# 7_-GSM_MODEM_MAIN.net
KiCad netlist of a schematic drawn in Altium Designer
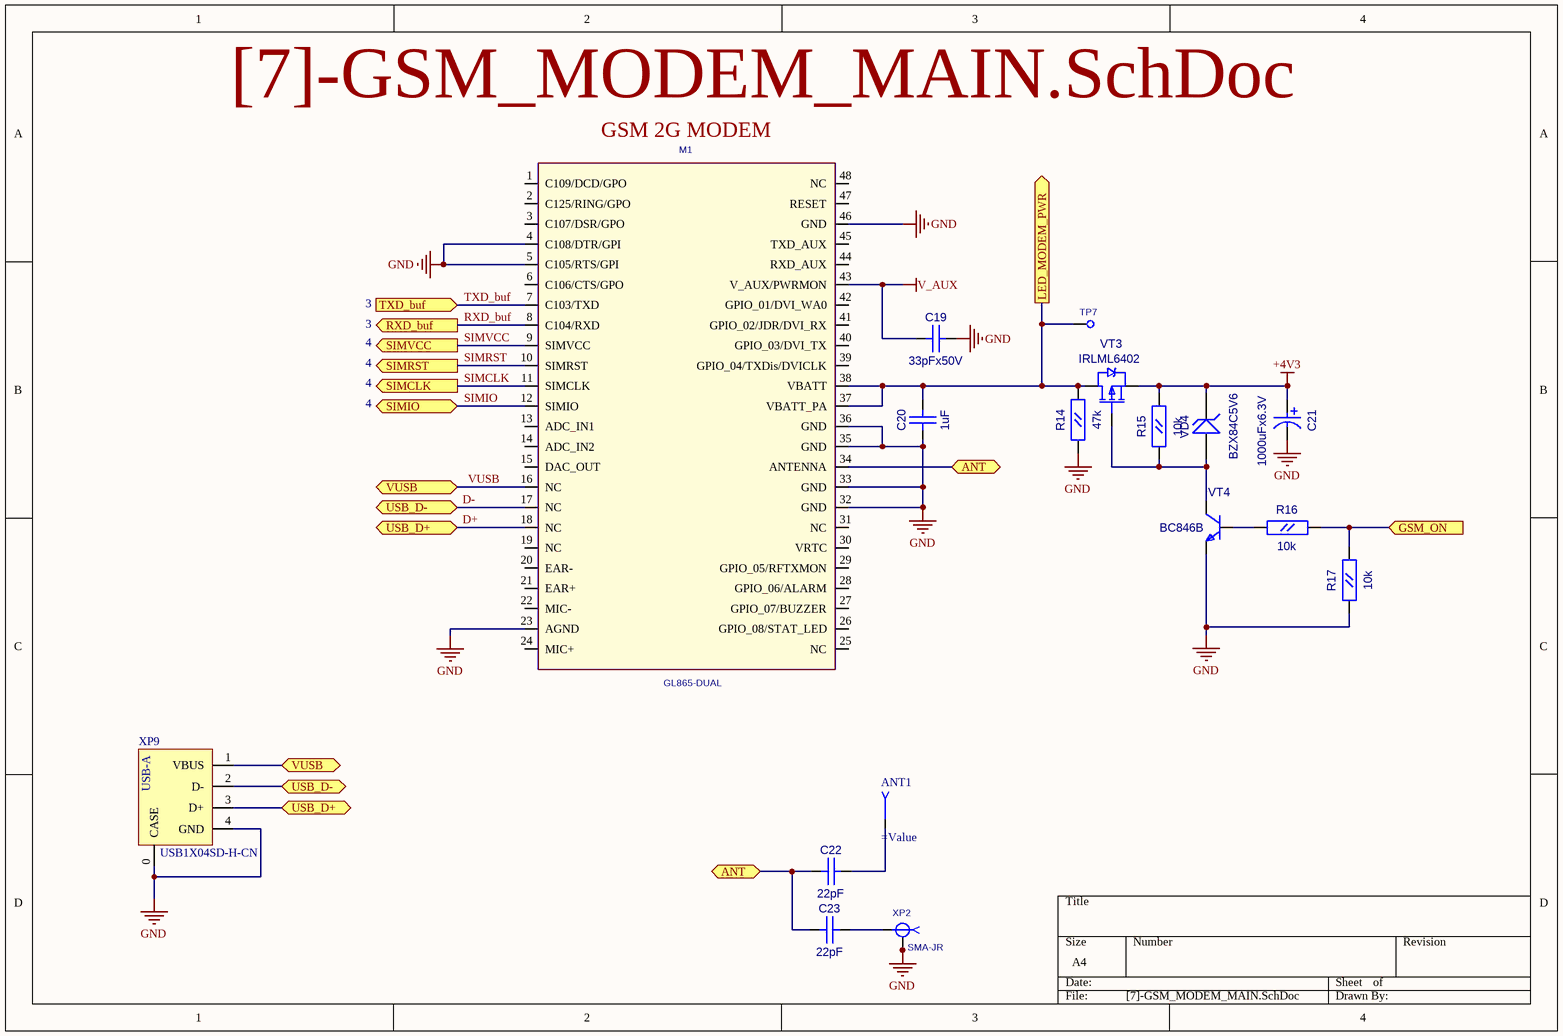
[diagram p0: [7]-GSM_MODEM_MAIN.SchDoc]

(export (version "E")
  (design (tool "Eeschema 10.0.6"))
  (components
    (comp (ref "ANT1")
      (value "~")
      (footprint "GSM_ANTENNA_MEANDER")
      (description "900-1800 Meandered GSM antenna 1.6mm FR4")
      (libsource (lib "fizik_lib") (part "GSM_ANTENNA_MEANDR"))
    )
    (comp (ref "C19")
      (value "33pFx50V")
      (footprint "CC0603")
      (description "CC0603")
      (libsource (lib "gprs_modem_2") (part "CC0603"))
    )
    (comp (ref "C20")
      (value "1uF")
      (footprint "CC0603")
      (description "CC0603")
      (libsource (lib "gprs_modem_2") (part "CC0603"))
    )
    (comp (ref "C21")
      (value "1000uFx6.3V")
      (footprint "CC8X3.5")
      (description "CAP0.35")
      (libsource (lib "fizik_lib") (part "CAP0.35"))
    )
    (comp (ref "C22")
      (value "22pF")
      (footprint "CC0603")
      (description "CC0603")
      (libsource (lib "gprs_modem_2") (part "CC0603"))
    )
    (comp (ref "C23")
      (value "22pF")
      (footprint "CC0603")
      (description "CC0603")
      (libsource (lib "gprs_modem_2") (part "CC0603"))
    )
    (comp (ref "M1")
      (value "GL865-DUAL")
      (footprint "GL868-DUAL")
      (description "GL868-DUAL")
      (libsource (lib "gprs_modem_2") (part "GL868-DUAL"))
    )
    (comp (ref "R14")
      (value "47k")
      (footprint "RC0603")
      (description "RC0603")
      (libsource (lib "gprs_modem_2") (part "RC0603"))
    )
    (comp (ref "R15")
      (value "10k")
      (footprint "RC0603")
      (description "RC0603")
      (libsource (lib "gprs_modem_2") (part "RC0603"))
    )
    (comp (ref "R16")
      (value "10k")
      (footprint "RC0603")
      (description "RC0603")
      (libsource (lib "gprs_modem_2") (part "RC0603"))
    )
    (comp (ref "R17")
      (value "10k")
      (footprint "RC0603")
      (description "RC0603")
      (libsource (lib "gprs_modem_2") (part "RC0603"))
    )
    (comp (ref "TP7")
      (value "TESTPOINT1")
      (footprint "TESTPOINT1")
      (libsource (lib "fizik_lib") (part "TESTPOINT1"))
    )
    (comp (ref "VD4")
      (value "BZX84C5V6")
      (footprint "SOT-23(123)")
      (description "Zener Voltage Regulator Diode")
      (libsource (lib "gprs_modem_2") (part "BZX84"))
    )
    (comp (ref "VT3")
      (value "IRLML6402")
      (footprint "SOT-23(123)")
      (description "HEXFET Power MOSFET")
      (libsource (lib "gprs_modem_2") (part "IRLML6402"))
    )
    (comp (ref "VT4")
      (value "BC846B")
      (footprint "SOT-23(123)")
      (description "BC846BLT1")
      (libsource (lib "gprs_modem_2") (part "BC846BLT1"))
    )
    (comp (ref "XP2") (value "SMA-JR") (footprint "SMA-JR") (libsource (lib "fizik_lib") (part "SMA-JR")))
    (comp (ref "XP9")
      (value "USB1X04SD-H-CN")
      (footprint "USB_A_FRONT")
      (description "Vertical USB connetctor,type A.THR")
      (libsource (lib "fizik_lib") (part "USB_A_VERTICAL"))
    )
  )
  (nets
    (net (code "1") (name "+4V3") (class "Default")
      (node (ref "C21") (pin "1") (pintype "passive"))
      (node (ref "R15") (pin "2") (pinfunction "B_2") (pintype "passive"))
      (node (ref "VD4") (pin "3") (pinfunction "K_3") (pintype "passive"))
      (node (ref "VT3") (pin "2") (pinfunction "S_2") (pintype "passive"))
    )
    (net (code "2") (name "/ANT") (class "Default")
      (node (ref "C22") (pin "1") (pinfunction "A_1") (pintype "passive"))
      (node (ref "C23") (pin "1") (pinfunction "A_1") (pintype "passive"))
      (node (ref "M1") (pin "34") (pinfunction "ANTENNA_34") (pintype "passive"))
    )
    (net (code "3") (name "/D+") (class "Default")
      (node (ref "M1") (pin "18") (pinfunction "NC_18") (pintype "passive"))
      (node (ref "XP9") (pin "3") (pinfunction "D+_3") (pintype "passive"))
    )
    (net (code "4") (name "/D-") (class "Default")
      (node (ref "M1") (pin "17") (pinfunction "NC_17") (pintype "passive"))
      (node (ref "XP9") (pin "2") (pinfunction "D-_2") (pintype "passive"))
    )
    (net (code "5") (name "/GSM_ON") (class "Default")
      (node (ref "R16") (pin "2") (pinfunction "B_2") (pintype "passive"))
      (node (ref "R17") (pin "2") (pinfunction "B_2") (pintype "passive"))
    )
    (net (code "6") (name "/LED_MODEM_PWR") (class "Default")
      (node (ref "C20") (pin "2") (pinfunction "B_2") (pintype "passive"))
      (node (ref "M1") (pin "37") (pinfunction "VBATT_PA_37") (pintype "passive"))
      (node (ref "M1") (pin "38") (pinfunction "VBATT_38") (pintype "passive"))
      (node (ref "R14") (pin "2") (pinfunction "B_2") (pintype "passive"))
      (node (ref "TP7") (pin "1") (pintype "passive"))
      (node (ref "VT3") (pin "3") (pinfunction "D_3") (pintype "passive"))
    )
    (net (code "7") (name "/RXD_buf") (class "Default")
      (node (ref "M1") (pin "8") (pinfunction "C104/RXD_8") (pintype "passive"))
    )
    (net (code "8") (name "/SIMCLK") (class "Default")
      (node (ref "M1") (pin "11") (pinfunction "SIMCLK_11") (pintype "passive"))
    )
    (net (code "9") (name "/SIMIO") (class "Default")
      (node (ref "M1") (pin "12") (pinfunction "SIMIO_12") (pintype "passive"))
    )
    (net (code "10") (name "/SIMRST") (class "Default")
      (node (ref "M1") (pin "10") (pinfunction "SIMRST_10") (pintype "passive"))
    )
    (net (code "11") (name "/SIMVCC") (class "Default")
      (node (ref "M1") (pin "9") (pinfunction "SIMVCC_9") (pintype "passive"))
    )
    (net (code "12") (name "/TXD_buf") (class "Default")
      (node (ref "M1") (pin "7") (pinfunction "C103/TXD_7") (pintype "passive"))
    )
    (net (code "13") (name "/VUSB") (class "Default")
      (node (ref "M1") (pin "16") (pinfunction "NC_16") (pintype "passive"))
      (node (ref "XP9") (pin "1") (pinfunction "VBUS_1") (pintype "passive"))
    )
    (net (code "14") (name "GND") (class "Default")
      (node (ref "C19") (pin "2") (pinfunction "B_2") (pintype "passive"))
      (node (ref "C20") (pin "1") (pinfunction "A_1") (pintype "passive"))
      (node (ref "C21") (pin "2") (pintype "passive"))
      (node (ref "M1") (pin "23") (pinfunction "AGND_23") (pintype "passive"))
      (node (ref "M1") (pin "32") (pinfunction "GND_32") (pintype "passive"))
      (node (ref "M1") (pin "33") (pinfunction "GND_33") (pintype "passive"))
      (node (ref "M1") (pin "35") (pinfunction "GND_35") (pintype "passive"))
      (node (ref "M1") (pin "36") (pinfunction "GND_36") (pintype "passive"))
      (node (ref "M1") (pin "4") (pinfunction "C108/DTR/GPI_4") (pintype "passive"))
      (node (ref "M1") (pin "46") (pinfunction "GND_46") (pintype "passive"))
      (node (ref "M1") (pin "5") (pinfunction "C105/RTS/GPI_5") (pintype "passive"))
      (node (ref "R14") (pin "1") (pinfunction "A_1") (pintype "passive"))
      (node (ref "R17") (pin "1") (pinfunction "A_1") (pintype "passive"))
      (node (ref "VT4") (pin "2") (pinfunction "E_2") (pintype "passive"))
      (node (ref "XP2") (pin "2") (pintype "passive"))
      (node (ref "XP2") (pin "3") (pintype "passive"))
      (node (ref "XP2") (pin "4") (pintype "passive"))
      (node (ref "XP2") (pin "5") (pintype "passive"))
      (node (ref "XP9") (pin "0") (pinfunction "CASE_0") (pintype "passive"))
      (node (ref "XP9") (pin "4") (pinfunction "GND_4") (pintype "passive"))
    )
    (net (code "15") (name "Net-(C22-B)") (class "Default")
      (node (ref "ANT1") (pin "1") (pintype "passive"))
      (node (ref "C22") (pin "2") (pinfunction "B_2") (pintype "passive"))
    )
    (net (code "16") (name "Net-(C23-B)") (class "Default")
      (node (ref "C23") (pin "2") (pinfunction "B_2") (pintype "passive"))
      (node (ref "XP2") (pin "1") (pintype "passive"))
    )
    (net (code "17") (name "Net-(R15-A)") (class "Default")
      (node (ref "R15") (pin "1") (pinfunction "A_1") (pintype "passive"))
      (node (ref "VD4") (pin "1") (pinfunction "A_1") (pintype "passive"))
      (node (ref "VT3") (pin "1") (pinfunction "G_1") (pintype "passive"))
      (node (ref "VT4") (pin "3") (pinfunction "C_3") (pintype "passive"))
    )
    (net (code "18") (name "Net-(R16-A)") (class "Default")
      (node (ref "R16") (pin "1") (pinfunction "A_1") (pintype "passive"))
      (node (ref "VT4") (pin "1") (pinfunction "B_1") (pintype "passive"))
    )
    (net (code "19") (name "V_AUX") (class "Default")
      (node (ref "C19") (pin "1") (pinfunction "A_1") (pintype "passive"))
      (node (ref "M1") (pin "43") (pinfunction "V_AUX/PWRMON_43") (pintype "passive"))
    )
    (net (code "20") (name "unconnected-(M1-ADC_IN1-Pad13)") (class "Default")
      (node (ref "M1") (pin "13") (pinfunction "ADC_IN1_13") (pintype "passive"))
    )
    (net (code "21") (name "unconnected-(M1-ADC_IN2-Pad14)") (class "Default")
      (node (ref "M1") (pin "14") (pinfunction "ADC_IN2_14") (pintype "passive"))
    )
    (net (code "22") (name "unconnected-(M1-C106{slash}CTS{slash}GPO-Pad6)") (class "Default")
      (node (ref "M1") (pin "6") (pinfunction "C106/CTS/GPO_6") (pintype "passive"))
    )
    (net (code "23") (name "unconnected-(M1-C107{slash}DSR{slash}GPO-Pad3)") (class "Default")
      (node (ref "M1") (pin "3") (pinfunction "C107/DSR/GPO_3") (pintype "passive"))
    )
    (net (code "24") (name "unconnected-(M1-C109{slash}DCD{slash}GPO-Pad1)") (class "Default")
      (node (ref "M1") (pin "1") (pinfunction "C109/DCD/GPO_1") (pintype "passive"))
    )
    (net (code "25") (name "unconnected-(M1-C125{slash}RING{slash}GPO-Pad2)") (class "Default")
      (node (ref "M1") (pin "2") (pinfunction "C125/RING/GPO_2") (pintype "passive"))
    )
    (net (code "26") (name "unconnected-(M1-DAC_OUT-Pad15)") (class "Default")
      (node (ref "M1") (pin "15") (pinfunction "DAC_OUT_15") (pintype "passive"))
    )
    (net (code "27") (name "unconnected-(M1-EAR+-Pad21)") (class "Default")
      (node (ref "M1") (pin "21") (pinfunction "EAR+_21") (pintype "passive"))
    )
    (net (code "28") (name "unconnected-(M1-EAR--Pad20)") (class "Default")
      (node (ref "M1") (pin "20") (pinfunction "EAR-_20") (pintype "passive"))
    )
    (net (code "29") (name "unconnected-(M1-GPIO_01{slash}DVI_WA0-Pad42)") (class "Default")
      (node (ref "M1") (pin "42") (pinfunction "GPIO_01/DVI_WA0_42") (pintype "passive"))
    )
    (net (code "30") (name "unconnected-(M1-GPIO_02{slash}JDR{slash}DVI_RX-Pad41)") (class "Default")
      (node (ref "M1") (pin "41") (pinfunction "GPIO_02/JDR/DVI_RX_41") (pintype "passive"))
    )
    (net (code "31") (name "unconnected-(M1-GPIO_03{slash}DVI_TX-Pad40)") (class "Default")
      (node (ref "M1") (pin "40") (pinfunction "GPIO_03/DVI_TX_40") (pintype "passive"))
    )
    (net (code "32") (name "unconnected-(M1-GPIO_04{slash}TXDis{slash}DVICLK-Pad39)") (class "Default")
      (node (ref "M1") (pin "39") (pinfunction "GPIO_04/TXDis/DVICLK_39") (pintype "passive"))
    )
    (net (code "33") (name "unconnected-(M1-GPIO_05{slash}RFTXMON-Pad29)") (class "Default")
      (node (ref "M1") (pin "29") (pinfunction "GPIO_05/RFTXMON_29") (pintype "passive"))
    )
    (net (code "34") (name "unconnected-(M1-GPIO_06{slash}ALARM-Pad28)") (class "Default")
      (node (ref "M1") (pin "28") (pinfunction "GPIO_06/ALARM_28") (pintype "passive"))
    )
    (net (code "35") (name "unconnected-(M1-GPIO_07{slash}BUZZER-Pad27)") (class "Default")
      (node (ref "M1") (pin "27") (pinfunction "GPIO_07/BUZZER_27") (pintype "passive"))
    )
    (net (code "36") (name "unconnected-(M1-GPIO_08{slash}STAT_LED-Pad26)") (class "Default")
      (node (ref "M1") (pin "26") (pinfunction "GPIO_08/STAT_LED_26") (pintype "passive"))
    )
    (net (code "37") (name "unconnected-(M1-MIC+-Pad24)") (class "Default")
      (node (ref "M1") (pin "24") (pinfunction "MIC+_24") (pintype "passive"))
    )
    (net (code "38") (name "unconnected-(M1-MIC--Pad22)") (class "Default")
      (node (ref "M1") (pin "22") (pinfunction "MIC-_22") (pintype "passive"))
    )
    (net (code "39") (name "unconnected-(M1-NC-Pad19)") (class "Default")
      (node (ref "M1") (pin "19") (pinfunction "NC_19") (pintype "passive"))
    )
    (net (code "40") (name "unconnected-(M1-NC-Pad25)") (class "Default")
      (node (ref "M1") (pin "25") (pinfunction "NC_25") (pintype "passive"))
    )
    (net (code "41") (name "unconnected-(M1-NC-Pad31)") (class "Default")
      (node (ref "M1") (pin "31") (pinfunction "NC_31") (pintype "passive"))
    )
    (net (code "42") (name "unconnected-(M1-NC-Pad48)") (class "Default")
      (node (ref "M1") (pin "48") (pinfunction "NC_48") (pintype "passive"))
    )
    (net (code "43") (name "unconnected-(M1-RESET-Pad47)") (class "Default")
      (node (ref "M1") (pin "47") (pinfunction "RESET_47") (pintype "passive"))
    )
    (net (code "44") (name "unconnected-(M1-RXD_AUX-Pad44)") (class "Default")
      (node (ref "M1") (pin "44") (pinfunction "RXD_AUX_44") (pintype "passive"))
    )
    (net (code "45") (name "unconnected-(M1-TXD_AUX-Pad45)") (class "Default")
      (node (ref "M1") (pin "45") (pinfunction "TXD_AUX_45") (pintype "passive"))
    )
    (net (code "46") (name "unconnected-(M1-VRTC-Pad30)") (class "Default")
      (node (ref "M1") (pin "30") (pinfunction "VRTC_30") (pintype "passive"))
    )
  )
)
